# Analog_Schematic.net
KiCad netlist of a schematic drawn in EAGLE
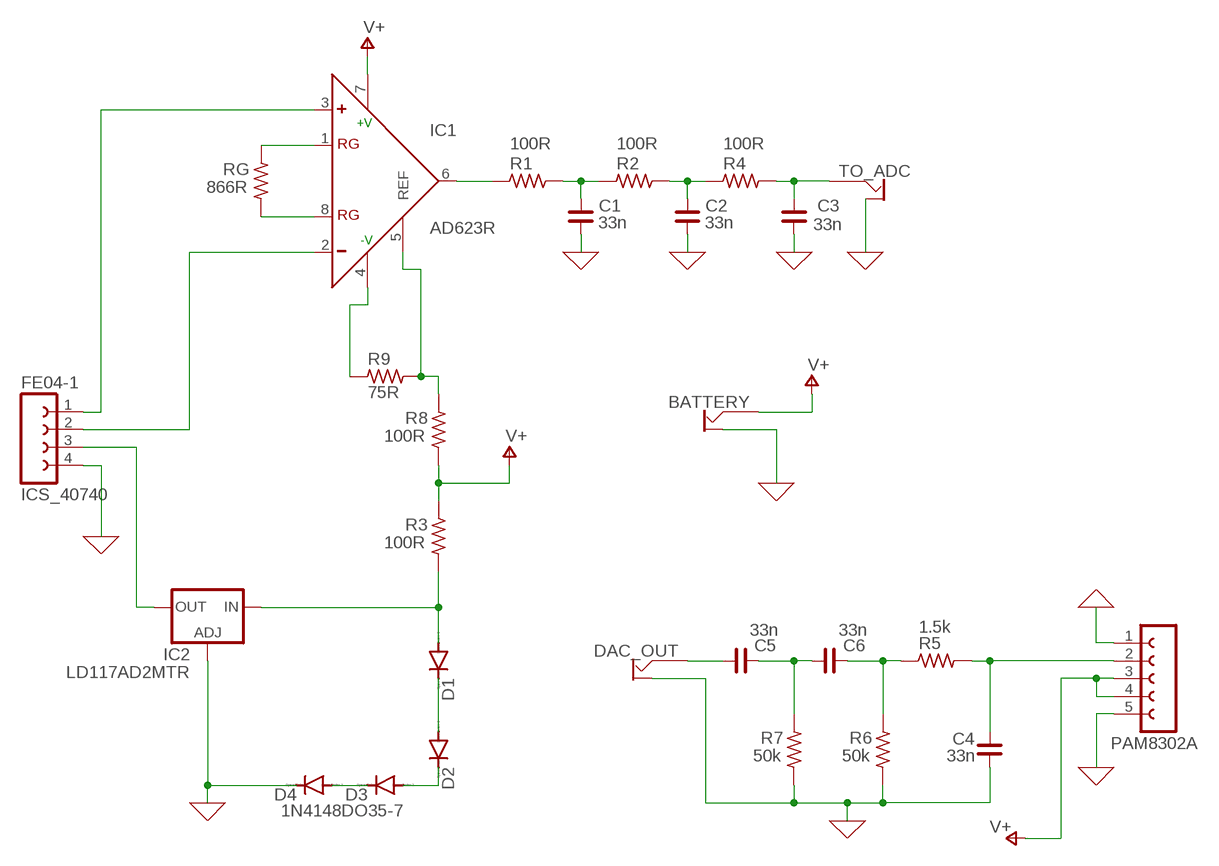
[diagram p0: schematic, sheet 1]

(export (version "E")
  (design (tool "Eeschema 10.0.6"))
  (components
    (comp (ref "BATTERY")
      (value "OFFBOARD2JACKALT")
      (footprint "eagle-import:OFFBOARD2JACKALT")
      (libsource (lib "eagle-import") (part "OFFBOARD2JACKALT"))
    )
    (comp (ref "C1")
      (value "33n")
      (footprint "eagle-import:C0603")
      (libsource (lib "eagle-import") (part "C_0603"))
    )
    (comp (ref "C2")
      (value "33n")
      (footprint "eagle-import:C0603")
      (libsource (lib "eagle-import") (part "C_0603"))
    )
    (comp (ref "C3")
      (value "33n")
      (footprint "eagle-import:C0603")
      (libsource (lib "eagle-import") (part "C_0603"))
    )
    (comp (ref "C4")
      (value "33n")
      (footprint "eagle-import:C0603")
      (libsource (lib "eagle-import") (part "C_0603"))
    )
    (comp (ref "C5")
      (value "33n")
      (footprint "eagle-import:C0603")
      (libsource (lib "eagle-import") (part "C_0603"))
    )
    (comp (ref "C6")
      (value "33n")
      (footprint "eagle-import:C0603")
      (libsource (lib "eagle-import") (part "C_0603"))
    )
    (comp (ref "D1")
      (value "1N4148DO35-7")
      (footprint "eagle-import:DO35-7")
      (libsource (lib "eagle-import") (part "1N4148DO35-7"))
    )
    (comp (ref "D2")
      (value "1N4148DO35-7")
      (footprint "eagle-import:DO35-7")
      (libsource (lib "eagle-import") (part "1N4148DO35-7"))
    )
    (comp (ref "D3")
      (value "1N4148DO35-7")
      (footprint "eagle-import:DO35-7")
      (libsource (lib "eagle-import") (part "1N4148DO35-7"))
    )
    (comp (ref "D4")
      (value "1N4148DO35-7")
      (footprint "eagle-import:DO35-7")
      (libsource (lib "eagle-import") (part "1N4148DO35-7"))
    )
    (comp (ref "DAC_OUT")
      (value "OFFBOARD2JACKALT")
      (footprint "eagle-import:OFFBOARD2JACKALT")
      (libsource (lib "eagle-import") (part "OFFBOARD2JACKALT"))
    )
    (comp (ref "IC1")
      (value "AD623R")
      (footprint "eagle-import:SO8")
      (fields (field (name "MPN") "AD623ARZ."))
      (libsource (lib "eagle-import") (part "AD623R"))
    )
    (comp (ref "IC2")
      (value "LD117AD2MTR")
      (footprint "eagle-import:D2PACK")
      (libsource (lib "eagle-import") (part "LD117A?D2MTR"))
    )
    (comp (ref "ICS_40740")
      (value "FE04-1")
      (footprint "eagle-import:FE04-1")
      (libsource (lib "eagle-import") (part "FE04-1"))
    )
    (comp (ref "PAM8302A")
      (value "FE05-1")
      (footprint "eagle-import:FE05-1")
      (libsource (lib "eagle-import") (part "FE05-1"))
    )
    (comp (ref "R1")
      (value "100R")
      (footprint "eagle-import:R0603")
      (libsource (lib "eagle-import") (part "R_0603"))
    )
    (comp (ref "R2")
      (value "100R")
      (footprint "eagle-import:R0603")
      (libsource (lib "eagle-import") (part "R_0603"))
    )
    (comp (ref "R3")
      (value "100R")
      (footprint "eagle-import:R0603")
      (libsource (lib "eagle-import") (part "R_0603"))
    )
    (comp (ref "R4")
      (value "100R")
      (footprint "eagle-import:R0603")
      (libsource (lib "eagle-import") (part "R_0603"))
    )
    (comp (ref "R5")
      (value "1.5k")
      (footprint "eagle-import:R0603")
      (libsource (lib "eagle-import") (part "R_0603"))
    )
    (comp (ref "R6")
      (value "50k")
      (footprint "eagle-import:R0603")
      (libsource (lib "eagle-import") (part "R_0603"))
    )
    (comp (ref "R7")
      (value "50k")
      (footprint "eagle-import:R0603")
      (libsource (lib "eagle-import") (part "R_0603"))
    )
    (comp (ref "R8")
      (value "100R")
      (footprint "eagle-import:R0603")
      (libsource (lib "eagle-import") (part "R_0603"))
    )
    (comp (ref "R9")
      (value "75R")
      (footprint "eagle-import:R0603")
      (libsource (lib "eagle-import") (part "R_0603"))
    )
    (comp (ref "RG")
      (value "866R")
      (footprint "eagle-import:R0603")
      (libsource (lib "eagle-import") (part "R_0603"))
    )
    (comp (ref "TO_ADC")
      (value "OFFBOARD2JACKALT")
      (footprint "eagle-import:OFFBOARD2JACKALT")
      (libsource (lib "eagle-import") (part "OFFBOARD2JACKALT"))
    )
  )
  (nets
    (net (code "1") (name "GND") (class "Default")
      (node (ref "BATTERY") (pin "GND") (pinfunction "GND_GND") (pintype "passive"))
      (node (ref "C1") (pin "2") (pinfunction "2_2") (pintype "passive"))
      (node (ref "C2") (pin "2") (pinfunction "2_2") (pintype "passive"))
      (node (ref "C3") (pin "2") (pinfunction "2_2") (pintype "passive"))
      (node (ref "C4") (pin "2") (pinfunction "2_2") (pintype "passive"))
      (node (ref "D4") (pin "C") (pinfunction "C_C") (pintype "passive"))
      (node (ref "DAC_OUT") (pin "GND") (pinfunction "GND_GND") (pintype "passive"))
      (node (ref "IC2") (pin "1") (pinfunction "ADJ_1") (pintype "input"))
      (node (ref "ICS_40740") (pin "4") (pinfunction "4_4") (pintype "passive"))
      (node (ref "PAM8302A") (pin "1") (pinfunction "1_1") (pintype "passive"))
      (node (ref "PAM8302A") (pin "5") (pinfunction "5_5") (pintype "passive"))
      (node (ref "R6") (pin "1") (pinfunction "1_1") (pintype "passive"))
      (node (ref "R7") (pin "1") (pinfunction "1_1") (pintype "passive"))
      (node (ref "TO_ADC") (pin "GND") (pinfunction "GND_GND") (pintype "passive"))
    )
    (net (code "2") (name "Net-(C1-Pad1)") (class "Default")
      (node (ref "C1") (pin "1") (pinfunction "1_1") (pintype "passive"))
      (node (ref "R1") (pin "2") (pinfunction "2_2") (pintype "passive"))
      (node (ref "R2") (pin "1") (pinfunction "1_1") (pintype "passive"))
    )
    (net (code "3") (name "Net-(C2-Pad1)") (class "Default")
      (node (ref "C2") (pin "1") (pinfunction "1_1") (pintype "passive"))
      (node (ref "R2") (pin "2") (pinfunction "2_2") (pintype "passive"))
      (node (ref "R4") (pin "1") (pinfunction "1_1") (pintype "passive"))
    )
    (net (code "4") (name "Net-(C3-Pad1)") (class "Default")
      (node (ref "C3") (pin "1") (pinfunction "1_1") (pintype "passive"))
      (node (ref "R4") (pin "2") (pinfunction "2_2") (pintype "passive"))
      (node (ref "TO_ADC") (pin "SIGNAL") (pinfunction "SIGNAL_SIGNAL") (pintype "passive"))
    )
    (net (code "5") (name "Net-(C4-Pad1)") (class "Default")
      (node (ref "C4") (pin "1") (pinfunction "1_1") (pintype "passive"))
      (node (ref "PAM8302A") (pin "2") (pinfunction "2_2") (pintype "passive"))
      (node (ref "R5") (pin "2") (pinfunction "2_2") (pintype "passive"))
    )
    (net (code "6") (name "Net-(C5-Pad1)") (class "Default")
      (node (ref "C5") (pin "1") (pinfunction "1_1") (pintype "passive"))
      (node (ref "DAC_OUT") (pin "SIGNAL") (pinfunction "SIGNAL_SIGNAL") (pintype "passive"))
    )
    (net (code "7") (name "Net-(C5-Pad2)") (class "Default")
      (node (ref "C5") (pin "2") (pinfunction "2_2") (pintype "passive"))
      (node (ref "C6") (pin "1") (pinfunction "1_1") (pintype "passive"))
      (node (ref "R7") (pin "2") (pinfunction "2_2") (pintype "passive"))
    )
    (net (code "8") (name "Net-(C6-Pad2)") (class "Default")
      (node (ref "C6") (pin "2") (pinfunction "2_2") (pintype "passive"))
      (node (ref "R5") (pin "1") (pinfunction "1_1") (pintype "passive"))
      (node (ref "R6") (pin "2") (pinfunction "2_2") (pintype "passive"))
    )
    (net (code "9") (name "Net-(D1-PadC)") (class "Default")
      (node (ref "D1") (pin "C") (pinfunction "C_C") (pintype "passive"))
      (node (ref "D2") (pin "A") (pinfunction "A_A") (pintype "passive"))
    )
    (net (code "10") (name "Net-(D2-PadC)") (class "Default")
      (node (ref "D2") (pin "C") (pinfunction "C_C") (pintype "passive"))
      (node (ref "D3") (pin "A") (pinfunction "A_A") (pintype "passive"))
    )
    (net (code "11") (name "Net-(D3-PadC)") (class "Default")
      (node (ref "D3") (pin "C") (pinfunction "C_C") (pintype "passive"))
      (node (ref "D4") (pin "A") (pinfunction "A_A") (pintype "passive"))
    )
    (net (code "12") (name "Net-(IC1-+)") (class "Default")
      (node (ref "IC1") (pin "3") (pinfunction "+_3") (pintype "input"))
      (node (ref "ICS_40740") (pin "1") (pinfunction "1_1") (pintype "passive"))
    )
    (net (code "13") (name "Net-(IC1--)") (class "Default")
      (node (ref "IC1") (pin "2") (pinfunction "-_2") (pintype "input"))
      (node (ref "ICS_40740") (pin "2") (pinfunction "2_2") (pintype "passive"))
    )
    (net (code "14") (name "Net-(IC1--V)") (class "Default")
      (node (ref "IC1") (pin "4") (pinfunction "-V_4") (pintype "power_in"))
      (node (ref "R9") (pin "1") (pinfunction "1_1") (pintype "passive"))
    )
    (net (code "15") (name "Net-(IC1-OUT)") (class "Default")
      (node (ref "IC1") (pin "6") (pinfunction "OUT_6") (pintype "output"))
      (node (ref "R1") (pin "1") (pinfunction "1_1") (pintype "passive"))
    )
    (net (code "16") (name "Net-(IC1-REF)") (class "Default")
      (node (ref "IC1") (pin "5") (pinfunction "REF_5") (pintype "passive"))
      (node (ref "R8") (pin "2") (pinfunction "2_2") (pintype "passive"))
      (node (ref "R9") (pin "2") (pinfunction "2_2") (pintype "passive"))
    )
    (net (code "17") (name "Net-(IC1-RG-Pad1)") (class "Default")
      (node (ref "IC1") (pin "1") (pinfunction "RG_1") (pintype "passive"))
      (node (ref "RG") (pin "2") (pinfunction "2_2") (pintype "passive"))
    )
    (net (code "18") (name "Net-(IC1-RG-Pad8)") (class "Default")
      (node (ref "IC1") (pin "8") (pinfunction "RG_8") (pintype "passive"))
      (node (ref "RG") (pin "1") (pinfunction "1_1") (pintype "passive"))
    )
    (net (code "19") (name "Net-(IC2-IN)") (class "Default")
      (node (ref "D1") (pin "A") (pinfunction "A_A") (pintype "passive"))
      (node (ref "IC2") (pin "3") (pinfunction "IN_3") (pintype "input"))
      (node (ref "R3") (pin "1") (pinfunction "1_1") (pintype "passive"))
    )
    (net (code "20") (name "Net-(IC2-OUT)") (class "Default")
      (node (ref "IC2") (pin "2") (pinfunction "OUT_2") (pintype "passive"))
      (node (ref "ICS_40740") (pin "3") (pinfunction "3_3") (pintype "passive"))
    )
    (net (code "21") (name "V+") (class "Default")
      (node (ref "BATTERY") (pin "SIGNAL") (pinfunction "SIGNAL_SIGNAL") (pintype "passive"))
      (node (ref "IC1") (pin "7") (pinfunction "+V_7") (pintype "power_in"))
      (node (ref "PAM8302A") (pin "3") (pinfunction "3_3") (pintype "passive"))
      (node (ref "PAM8302A") (pin "4") (pinfunction "4_4") (pintype "passive"))
      (node (ref "R3") (pin "2") (pinfunction "2_2") (pintype "passive"))
      (node (ref "R8") (pin "1") (pinfunction "1_1") (pintype "passive"))
    )
  )
)
